# bldc-robot-main-board-2016.net
KiCad netlist of a schematic drawn in Altium Designer
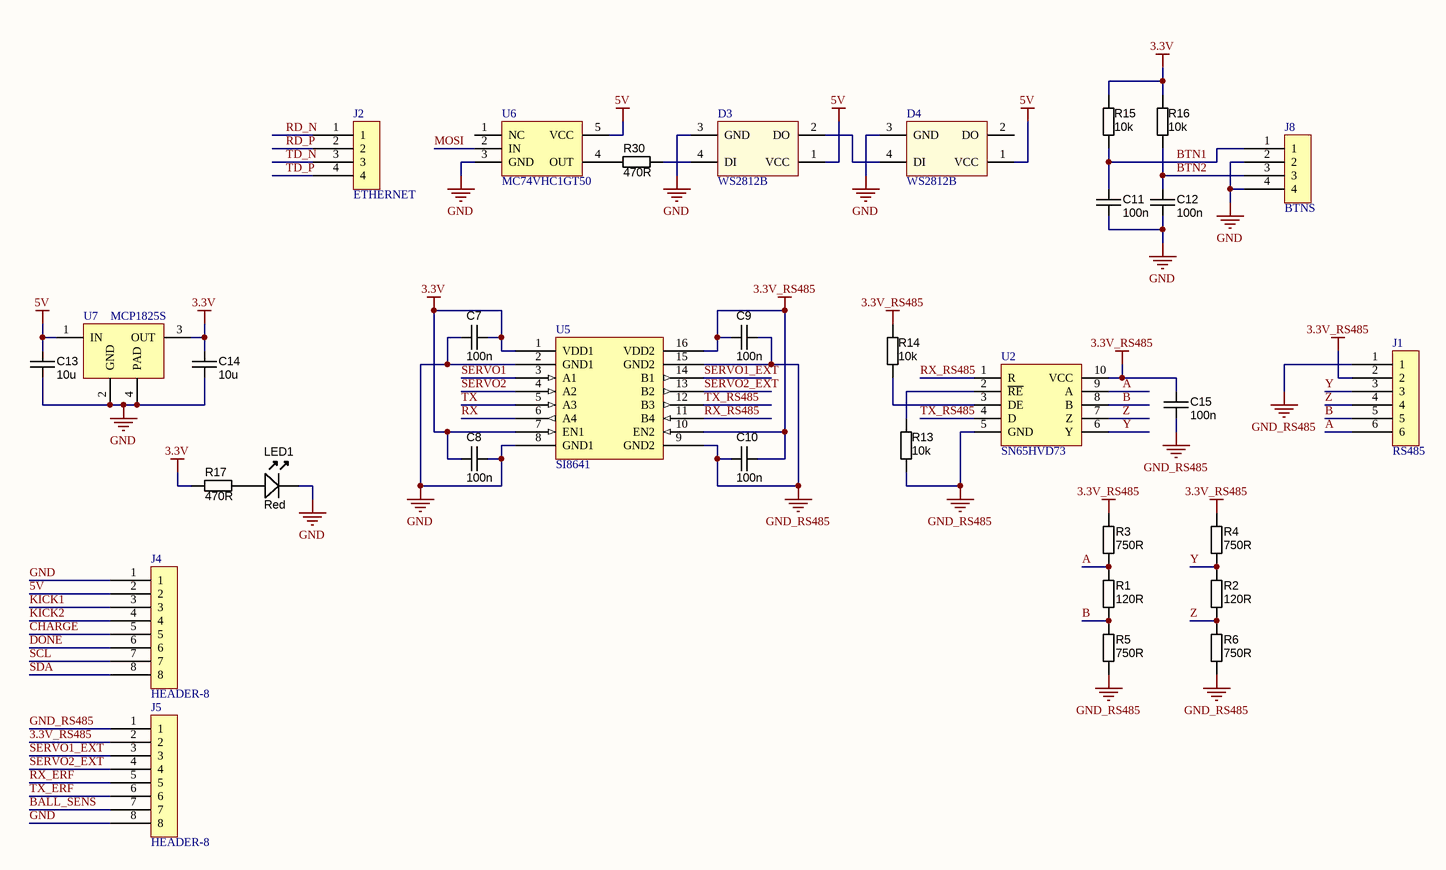
[diagram p0: bldc-robot-main-board-2016.SchDoc]

(export (version "E")
  (design (tool "Eeschema 10.0.6"))
  (components
    (comp (ref "C7")
      (value "100n")
      (footprint "CAPC1608X90N")
      (description "Capacitor SMD Cer 100nF 10% 50V X7R 0603")
      (fields (field (name "TOLERANCE") "±10%"))
      (libsource (lib "PBL - Capacitors") (part "CAPC_100n_0603_X7R_50V_10%"))
    )
    (comp (ref "C8")
      (value "100n")
      (footprint "CAPC1608X90N")
      (description "Capacitor SMD Cer 100nF 10% 50V X7R 0603")
      (fields (field (name "TOLERANCE") "±10%"))
      (libsource (lib "PBL - Capacitors") (part "CAPC_100n_0603_X7R_50V_10%"))
    )
    (comp (ref "C9")
      (value "100n")
      (footprint "CAPC1608X90N")
      (description "Capacitor SMD Cer 100nF 10% 50V X7R 0603")
      (fields (field (name "TOLERANCE") "±10%"))
      (libsource (lib "PBL - Capacitors") (part "CAPC_100n_0603_X7R_50V_10%"))
    )
    (comp (ref "C10")
      (value "100n")
      (footprint "CAPC1608X90N")
      (description "Capacitor SMD Cer 100nF 10% 50V X7R 0603")
      (fields (field (name "TOLERANCE") "±10%"))
      (libsource (lib "PBL - Capacitors") (part "CAPC_100n_0603_X7R_50V_10%"))
    )
    (comp (ref "C11")
      (value "100n")
      (footprint "CAPC1608X90N")
      (description "Capacitor SMD Cer 100nF 10% 50V X7R 0603")
      (fields (field (name "TOLERANCE") "±10%"))
      (libsource (lib "PBL - Capacitors") (part "CAPC_100n_0603_X7R_50V_10%"))
    )
    (comp (ref "C12")
      (value "100n")
      (footprint "CAPC1608X90N")
      (description "Capacitor SMD Cer 100nF 10% 50V X7R 0603")
      (fields (field (name "TOLERANCE") "±10%"))
      (libsource (lib "PBL - Capacitors") (part "CAPC_100n_0603_X7R_50V_10%"))
    )
    (comp (ref "C13")
      (value "10u")
      (footprint "CAPC3216X180N")
      (description "Capacitor SMD Cer 10uF 10% 10V X5R 1206")
      (fields (field (name "TOLERANCE") "±10%"))
      (libsource (lib "PBL - Capacitors") (part "CAPC_10u_1206_10V"))
    )
    (comp (ref "C14")
      (value "10u")
      (footprint "CAPC3216X180N")
      (description "Capacitor SMD Cer 10uF 10% 10V X5R 1206")
      (fields (field (name "TOLERANCE") "±10%"))
      (libsource (lib "PBL - Capacitors") (part "CAPC_10u_1206_10V"))
    )
    (comp (ref "C15")
      (value "100n")
      (footprint "CAPC1608X90N")
      (description "Capacitor SMD Cer 100nF 10% 50V X7R 0603")
      (fields (field (name "TOLERANCE") "±10%"))
      (libsource (lib "PBL - Capacitors") (part "CAPC_100n_0603_X7R_50V_10%"))
    )
    (comp (ref "D3") (value "WS2812B") (footprint "WS2812B") (libsource (lib "misc") (part "WS2812B")))
    (comp (ref "D4") (value "WS2812B") (footprint "WS2812B") (libsource (lib "misc") (part "WS2812B")))
    (comp (ref "J1")
      (value "RS485")
      (footprint "MICRO-MATCH-6")
      (libsource (lib "connectors") (part "HEADER-6"))
    )
    (comp (ref "J2")
      (value "ETHERNET")
      (footprint "MICRO-MATCH-4")
      (libsource (lib "connectors") (part "HEADER-4"))
    )
    (comp (ref "J4")
      (value "HEADER-8")
      (footprint "MICRO-MATCH-8")
      (libsource (lib "connectors") (part "HEADER-8"))
    )
    (comp (ref "J5")
      (value "HEADER-8")
      (footprint "MICRO-MATCH-8")
      (libsource (lib "connectors") (part "HEADER-8"))
    )
    (comp (ref "J8")
      (value "BTNS")
      (footprint "MICRO-MATCH-4")
      (libsource (lib "connectors") (part "HEADER-4"))
    )
    (comp (ref "LED1")
      (value "Red")
      (footprint "LED-0603-RED")
      (description "LED 0603 SMD Hyper Red 630nm 220mcd 20mA")
      (libsource (lib "PBL - Light Sources") (part "LED_SMD_Red_0603_220mcd"))
    )
    (comp (ref "R1")
      (value "120R")
      (footprint "RESC1608X55N")
      (description "Resistor SMD chip 120 Ohm 0.1W 5% 0603")
      (fields (field (name "TOLERANCE") "±5%"))
      (libsource (lib "") (part "RES_120R_0603_5%_1"))
    )
    (comp (ref "R2")
      (value "120R")
      (footprint "RESC1608X55N")
      (description "Resistor SMD chip 120 Ohm 0.1W 5% 0603")
      (fields (field (name "TOLERANCE") "±5%"))
      (libsource (lib "") (part "RES_120R_0603_5%_1"))
    )
    (comp (ref "R3")
      (value "750R")
      (footprint "RESC1608X55N")
      (description "Resistor SMD chip 120 Ohm 0.1W 5% 0603")
      (fields (field (name "TOLERANCE") "±5%"))
      (libsource (lib "") (part "RES_120R_0603_5%_1"))
    )
    (comp (ref "R4")
      (value "750R")
      (footprint "RESC1608X55N")
      (description "Resistor SMD chip 120 Ohm 0.1W 5% 0603")
      (fields (field (name "TOLERANCE") "±5%"))
      (libsource (lib "") (part "RES_120R_0603_5%_1"))
    )
    (comp (ref "R5")
      (value "750R")
      (footprint "RESC1608X55N")
      (description "Resistor SMD chip 120 Ohm 0.1W 5% 0603")
      (fields (field (name "TOLERANCE") "±5%"))
      (libsource (lib "") (part "RES_120R_0603_5%_1"))
    )
    (comp (ref "R6")
      (value "750R")
      (footprint "RESC1608X55N")
      (description "Resistor SMD chip 120 Ohm 0.1W 5% 0603")
      (fields (field (name "TOLERANCE") "±5%"))
      (libsource (lib "") (part "RES_120R_0603_5%_1"))
    )
    (comp (ref "R13")
      (value "10k")
      (footprint "RESC1608X55N")
      (description "Resistor SMD chip 120 Ohm 0.1W 5% 0603")
      (fields (field (name "TOLERANCE") "±5%"))
      (libsource (lib "PBL - Resistors") (part "RES_120R_0603_5%"))
    )
    (comp (ref "R14")
      (value "10k")
      (footprint "RESC1608X55N")
      (description "Resistor SMD chip 120 Ohm 0.1W 5% 0603")
      (fields (field (name "TOLERANCE") "±5%"))
      (libsource (lib "PBL - Resistors") (part "RES_120R_0603_5%"))
    )
    (comp (ref "R15")
      (value "10k")
      (footprint "RESC1608X55N")
      (description "Resistor SMD chip 120 Ohm 0.1W 5% 0603")
      (fields (field (name "TOLERANCE") "±5%"))
      (libsource (lib "PBL - Resistors") (part "RES_120R_0603_5%"))
    )
    (comp (ref "R16")
      (value "10k")
      (footprint "RESC1608X55N")
      (description "Resistor SMD chip 120 Ohm 0.1W 5% 0603")
      (fields (field (name "TOLERANCE") "±5%"))
      (libsource (lib "PBL - Resistors") (part "RES_120R_0603_5%"))
    )
    (comp (ref "R17")
      (value "470R")
      (footprint "RESC1608X55N")
      (description "Resistor SMD chip 120 Ohm 0.1W 5% 0603")
      (fields (field (name "TOLERANCE") "±5%"))
      (libsource (lib "") (part "RES_120R_0603_5%_2"))
    )
    (comp (ref "R30")
      (value "470R")
      (footprint "RESC1608X55N")
      (description "Resistor SMD chip 120 Ohm 0.1W 5% 0603")
      (fields (field (name "TOLERANCE") "±5%"))
      (libsource (lib "") (part "RES_120R_0603_5%_2"))
    )
    (comp (ref "U2")
      (value "SN65HVD73")
      (footprint "SOP10")
      (libsource (lib "texas_instruments") (part "SN65HVD3086E"))
    )
    (comp (ref "U5") (value "SI8641") (footprint "SOIC16") (libsource (lib "digital") (part "SI8641")))
    (comp (ref "U6")
      (value "MC74VHC1GT50")
      (footprint "SC70-5")
      (libsource (lib "digital") (part "MC74VHC1GT50"))
    )
    (comp (ref "U7")
      (value "MCP1825S")
      (footprint "SOT230P700X180-4N")
      (libsource (lib "power") (part "MIC5239"))
    )
  )
  (nets
    (net (code "1") (name "/A") (class "Default")
      (node (ref "J1") (pin "6") (pinfunction "6_6") (pintype "passive"))
      (node (ref "R1") (pin "1") (pinfunction "1_1") (pintype "passive"))
      (node (ref "R3") (pin "2") (pinfunction "2_2") (pintype "passive"))
      (node (ref "U2") (pin "9") (pinfunction "A_9") (pintype "passive"))
    )
    (net (code "2") (name "/B") (class "Default")
      (node (ref "J1") (pin "5") (pinfunction "5_5") (pintype "passive"))
      (node (ref "R1") (pin "2") (pinfunction "2_2") (pintype "passive"))
      (node (ref "R5") (pin "1") (pinfunction "1_1") (pintype "passive"))
      (node (ref "U2") (pin "8") (pinfunction "B_8") (pintype "passive"))
    )
    (net (code "3") (name "/BALL_SENS") (class "Default")
      (node (ref "J5") (pin "7") (pinfunction "7_7") (pintype "passive"))
    )
    (net (code "4") (name "/BTN1") (class "Default")
      (node (ref "C11") (pin "1") (pintype "passive"))
      (node (ref "J8") (pin "1") (pinfunction "1_1") (pintype "passive"))
      (node (ref "R15") (pin "1") (pinfunction "1_1") (pintype "passive"))
    )
    (net (code "5") (name "/BTN2") (class "Default")
      (node (ref "C12") (pin "1") (pintype "passive"))
      (node (ref "J8") (pin "3") (pinfunction "3_3") (pintype "passive"))
      (node (ref "R16") (pin "1") (pinfunction "1_1") (pintype "passive"))
    )
    (net (code "6") (name "/CHARGE") (class "Default")
      (node (ref "J4") (pin "5") (pinfunction "5_5") (pintype "passive"))
    )
    (net (code "7") (name "/DONE") (class "Default")
      (node (ref "J4") (pin "6") (pinfunction "6_6") (pintype "passive"))
    )
    (net (code "8") (name "/KICK1") (class "Default")
      (node (ref "J4") (pin "3") (pinfunction "3_3") (pintype "passive"))
    )
    (net (code "9") (name "/KICK2") (class "Default")
      (node (ref "J4") (pin "4") (pinfunction "4_4") (pintype "passive"))
    )
    (net (code "10") (name "/MOSI") (class "Default")
      (node (ref "U6") (pin "2") (pinfunction "IN_2") (pintype "passive"))
    )
    (net (code "11") (name "/RD_N") (class "Default")
      (node (ref "J2") (pin "1") (pinfunction "1_1") (pintype "passive"))
    )
    (net (code "12") (name "/RD_P") (class "Default")
      (node (ref "J2") (pin "2") (pinfunction "2_2") (pintype "passive"))
    )
    (net (code "13") (name "/RX") (class "Default")
      (node (ref "U5") (pin "6") (pinfunction "A4_6") (pintype "output"))
    )
    (net (code "14") (name "/RX_ERF") (class "Default")
      (node (ref "J5") (pin "5") (pinfunction "5_5") (pintype "passive"))
    )
    (net (code "15") (name "/RX_RS485") (class "Default")
      (node (ref "U2") (pin "1") (pinfunction "R_1") (pintype "passive"))
      (node (ref "U5") (pin "11") (pinfunction "B4_11") (pintype "input"))
    )
    (net (code "16") (name "/SCL") (class "Default")
      (node (ref "J4") (pin "7") (pinfunction "7_7") (pintype "passive"))
    )
    (net (code "17") (name "/SDA") (class "Default")
      (node (ref "J4") (pin "8") (pinfunction "8_8") (pintype "passive"))
    )
    (net (code "18") (name "/SERVO1") (class "Default")
      (node (ref "U5") (pin "3") (pinfunction "A1_3") (pintype "input"))
    )
    (net (code "19") (name "/SERVO1_EXT") (class "Default")
      (node (ref "J5") (pin "3") (pinfunction "3_3") (pintype "passive"))
      (node (ref "U5") (pin "14") (pinfunction "B1_14") (pintype "output"))
    )
    (net (code "20") (name "/SERVO2") (class "Default")
      (node (ref "U5") (pin "4") (pinfunction "A2_4") (pintype "input"))
    )
    (net (code "21") (name "/SERVO2_EXT") (class "Default")
      (node (ref "J5") (pin "4") (pinfunction "4_4") (pintype "passive"))
      (node (ref "U5") (pin "13") (pinfunction "B2_13") (pintype "output"))
    )
    (net (code "22") (name "/TD_N") (class "Default")
      (node (ref "J2") (pin "3") (pinfunction "3_3") (pintype "passive"))
    )
    (net (code "23") (name "/TD_P") (class "Default")
      (node (ref "J2") (pin "4") (pinfunction "4_4") (pintype "passive"))
    )
    (net (code "24") (name "/TX") (class "Default")
      (node (ref "U5") (pin "5") (pinfunction "A3_5") (pintype "input"))
    )
    (net (code "25") (name "/TX_ERF") (class "Default")
      (node (ref "J5") (pin "6") (pinfunction "6_6") (pintype "passive"))
    )
    (net (code "26") (name "/TX_RS485") (class "Default")
      (node (ref "U2") (pin "4") (pinfunction "D_4") (pintype "passive"))
      (node (ref "U5") (pin "12") (pinfunction "B3_12") (pintype "output"))
    )
    (net (code "27") (name "/Y") (class "Default")
      (node (ref "J1") (pin "3") (pinfunction "3_3") (pintype "passive"))
      (node (ref "R2") (pin "1") (pinfunction "1_1") (pintype "passive"))
      (node (ref "R4") (pin "2") (pinfunction "2_2") (pintype "passive"))
      (node (ref "U2") (pin "6") (pinfunction "Y_6") (pintype "passive"))
    )
    (net (code "28") (name "/Z") (class "Default")
      (node (ref "J1") (pin "4") (pinfunction "4_4") (pintype "passive"))
      (node (ref "R2") (pin "2") (pinfunction "2_2") (pintype "passive"))
      (node (ref "R6") (pin "1") (pinfunction "1_1") (pintype "passive"))
      (node (ref "U2") (pin "7") (pinfunction "Z_7") (pintype "passive"))
    )
    (net (code "29") (name "3.3V") (class "Default")
      (node (ref "C14") (pin "1") (pintype "passive"))
      (node (ref "C7") (pin "1") (pintype "passive"))
      (node (ref "C8") (pin "2") (pintype "passive"))
      (node (ref "R15") (pin "2") (pinfunction "2_2") (pintype "passive"))
      (node (ref "R16") (pin "2") (pinfunction "2_2") (pintype "passive"))
      (node (ref "R17") (pin "2") (pinfunction "2_2") (pintype "passive"))
      (node (ref "U5") (pin "1") (pinfunction "VDD1_1") (pintype "power_in"))
      (node (ref "U5") (pin "7") (pinfunction "EN1_7") (pintype "input"))
      (node (ref "U7") (pin "3") (pinfunction "OUT_3") (pintype "power_in"))
    )
    (net (code "30") (name "3.3V_RS485") (class "Default")
      (node (ref "C10") (pin "1") (pintype "passive"))
      (node (ref "C15") (pin "1") (pintype "passive"))
      (node (ref "C9") (pin "2") (pintype "passive"))
      (node (ref "J1") (pin "2") (pinfunction "2_2") (pintype "passive"))
      (node (ref "J5") (pin "2") (pinfunction "2_2") (pintype "passive"))
      (node (ref "R14") (pin "2") (pinfunction "2_2") (pintype "passive"))
      (node (ref "R3") (pin "1") (pinfunction "1_1") (pintype "passive"))
      (node (ref "R4") (pin "1") (pinfunction "1_1") (pintype "passive"))
      (node (ref "U2") (pin "10") (pinfunction "VCC_10") (pintype "passive"))
      (node (ref "U5") (pin "10") (pinfunction "EN2_10") (pintype "input"))
      (node (ref "U5") (pin "16") (pinfunction "VDD2_16") (pintype "power_in"))
    )
    (net (code "31") (name "5V") (class "Default")
      (node (ref "C13") (pin "1") (pintype "passive"))
      (node (ref "D3") (pin "1") (pinfunction "VCC_1") (pintype "passive"))
      (node (ref "D4") (pin "1") (pinfunction "VCC_1") (pintype "passive"))
      (node (ref "J4") (pin "2") (pinfunction "2_2") (pintype "passive"))
      (node (ref "U6") (pin "5") (pinfunction "VCC_5") (pintype "passive"))
      (node (ref "U7") (pin "1") (pinfunction "IN_1") (pintype "power_in"))
    )
    (net (code "32") (name "GND") (class "Default")
      (node (ref "C11") (pin "2") (pintype "passive"))
      (node (ref "C12") (pin "2") (pintype "passive"))
      (node (ref "C13") (pin "2") (pintype "passive"))
      (node (ref "C14") (pin "2") (pintype "passive"))
      (node (ref "C7") (pin "2") (pintype "passive"))
      (node (ref "C8") (pin "1") (pintype "passive"))
      (node (ref "D3") (pin "3") (pinfunction "GND_3") (pintype "passive"))
      (node (ref "D4") (pin "3") (pinfunction "GND_3") (pintype "passive"))
      (node (ref "J4") (pin "1") (pinfunction "1_1") (pintype "passive"))
      (node (ref "J5") (pin "8") (pinfunction "8_8") (pintype "passive"))
      (node (ref "J8") (pin "2") (pinfunction "2_2") (pintype "passive"))
      (node (ref "J8") (pin "4") (pinfunction "4_4") (pintype "passive"))
      (node (ref "LED1") (pin "K") (pinfunction "K_K") (pintype "passive"))
      (node (ref "U5") (pin "2") (pinfunction "GND1_2") (pintype "power_in"))
      (node (ref "U5") (pin "8") (pinfunction "GND1_8") (pintype "power_in"))
      (node (ref "U6") (pin "3") (pinfunction "GND_3") (pintype "passive"))
      (node (ref "U7") (pin "2") (pinfunction "GND_2") (pintype "power_in"))
      (node (ref "U7") (pin "4") (pinfunction "PAD_4") (pintype "power_in"))
    )
    (net (code "33") (name "GND_RS485") (class "Default")
      (node (ref "C10") (pin "2") (pintype "passive"))
      (node (ref "C15") (pin "2") (pintype "passive"))
      (node (ref "C9") (pin "1") (pintype "passive"))
      (node (ref "J1") (pin "1") (pinfunction "1_1") (pintype "passive"))
      (node (ref "J5") (pin "1") (pinfunction "1_1") (pintype "passive"))
      (node (ref "R13") (pin "1") (pinfunction "1_1") (pintype "passive"))
      (node (ref "R5") (pin "2") (pinfunction "2_2") (pintype "passive"))
      (node (ref "R6") (pin "2") (pinfunction "2_2") (pintype "passive"))
      (node (ref "U2") (pin "5") (pinfunction "GND_5") (pintype "passive"))
      (node (ref "U5") (pin "15") (pinfunction "GND2_15") (pintype "power_in"))
      (node (ref "U5") (pin "9") (pinfunction "GND2_9") (pintype "power_in"))
    )
    (net (code "34") (name "Net-(D3-DI)") (class "Default")
      (node (ref "D3") (pin "4") (pinfunction "DI_4") (pintype "passive"))
      (node (ref "R30") (pin "1") (pinfunction "1_1") (pintype "passive"))
    )
    (net (code "35") (name "Net-(D3-DO)") (class "Default")
      (node (ref "D3") (pin "2") (pinfunction "DO_2") (pintype "passive"))
      (node (ref "D4") (pin "4") (pinfunction "DI_4") (pintype "passive"))
    )
    (net (code "36") (name "Net-(LED1-PadA)") (class "Default")
      (node (ref "LED1") (pin "A") (pinfunction "A_A") (pintype "passive"))
      (node (ref "R17") (pin "1") (pinfunction "1_1") (pintype "passive"))
    )
    (net (code "37") (name "Net-(U2-DE)") (class "Default")
      (node (ref "R14") (pin "1") (pinfunction "1_1") (pintype "passive"))
      (node (ref "U2") (pin "3") (pinfunction "DE_3") (pintype "passive"))
    )
    (net (code "38") (name "Net-(U2-~{RE})") (class "Default")
      (node (ref "R13") (pin "2") (pinfunction "2_2") (pintype "passive"))
      (node (ref "U2") (pin "2") (pinfunction "~{RE}_2") (pintype "passive"))
    )
    (net (code "39") (name "Net-(U6-OUT)") (class "Default")
      (node (ref "R30") (pin "2") (pinfunction "2_2") (pintype "passive"))
      (node (ref "U6") (pin "4") (pinfunction "OUT_4") (pintype "passive"))
    )
    (net (code "40") (name "unconnected-(D4-DO-Pad2)") (class "Default")
      (node (ref "D4") (pin "2") (pinfunction "DO_2") (pintype "passive"))
    )
    (net (code "41") (name "unconnected-(U6-NC-Pad1)") (class "Default")
      (node (ref "U6") (pin "1") (pinfunction "NC_1") (pintype "passive"))
    )
  )
)
